# express_pre_power.net
KiCad netlist of a schematic drawn in Altium Designer
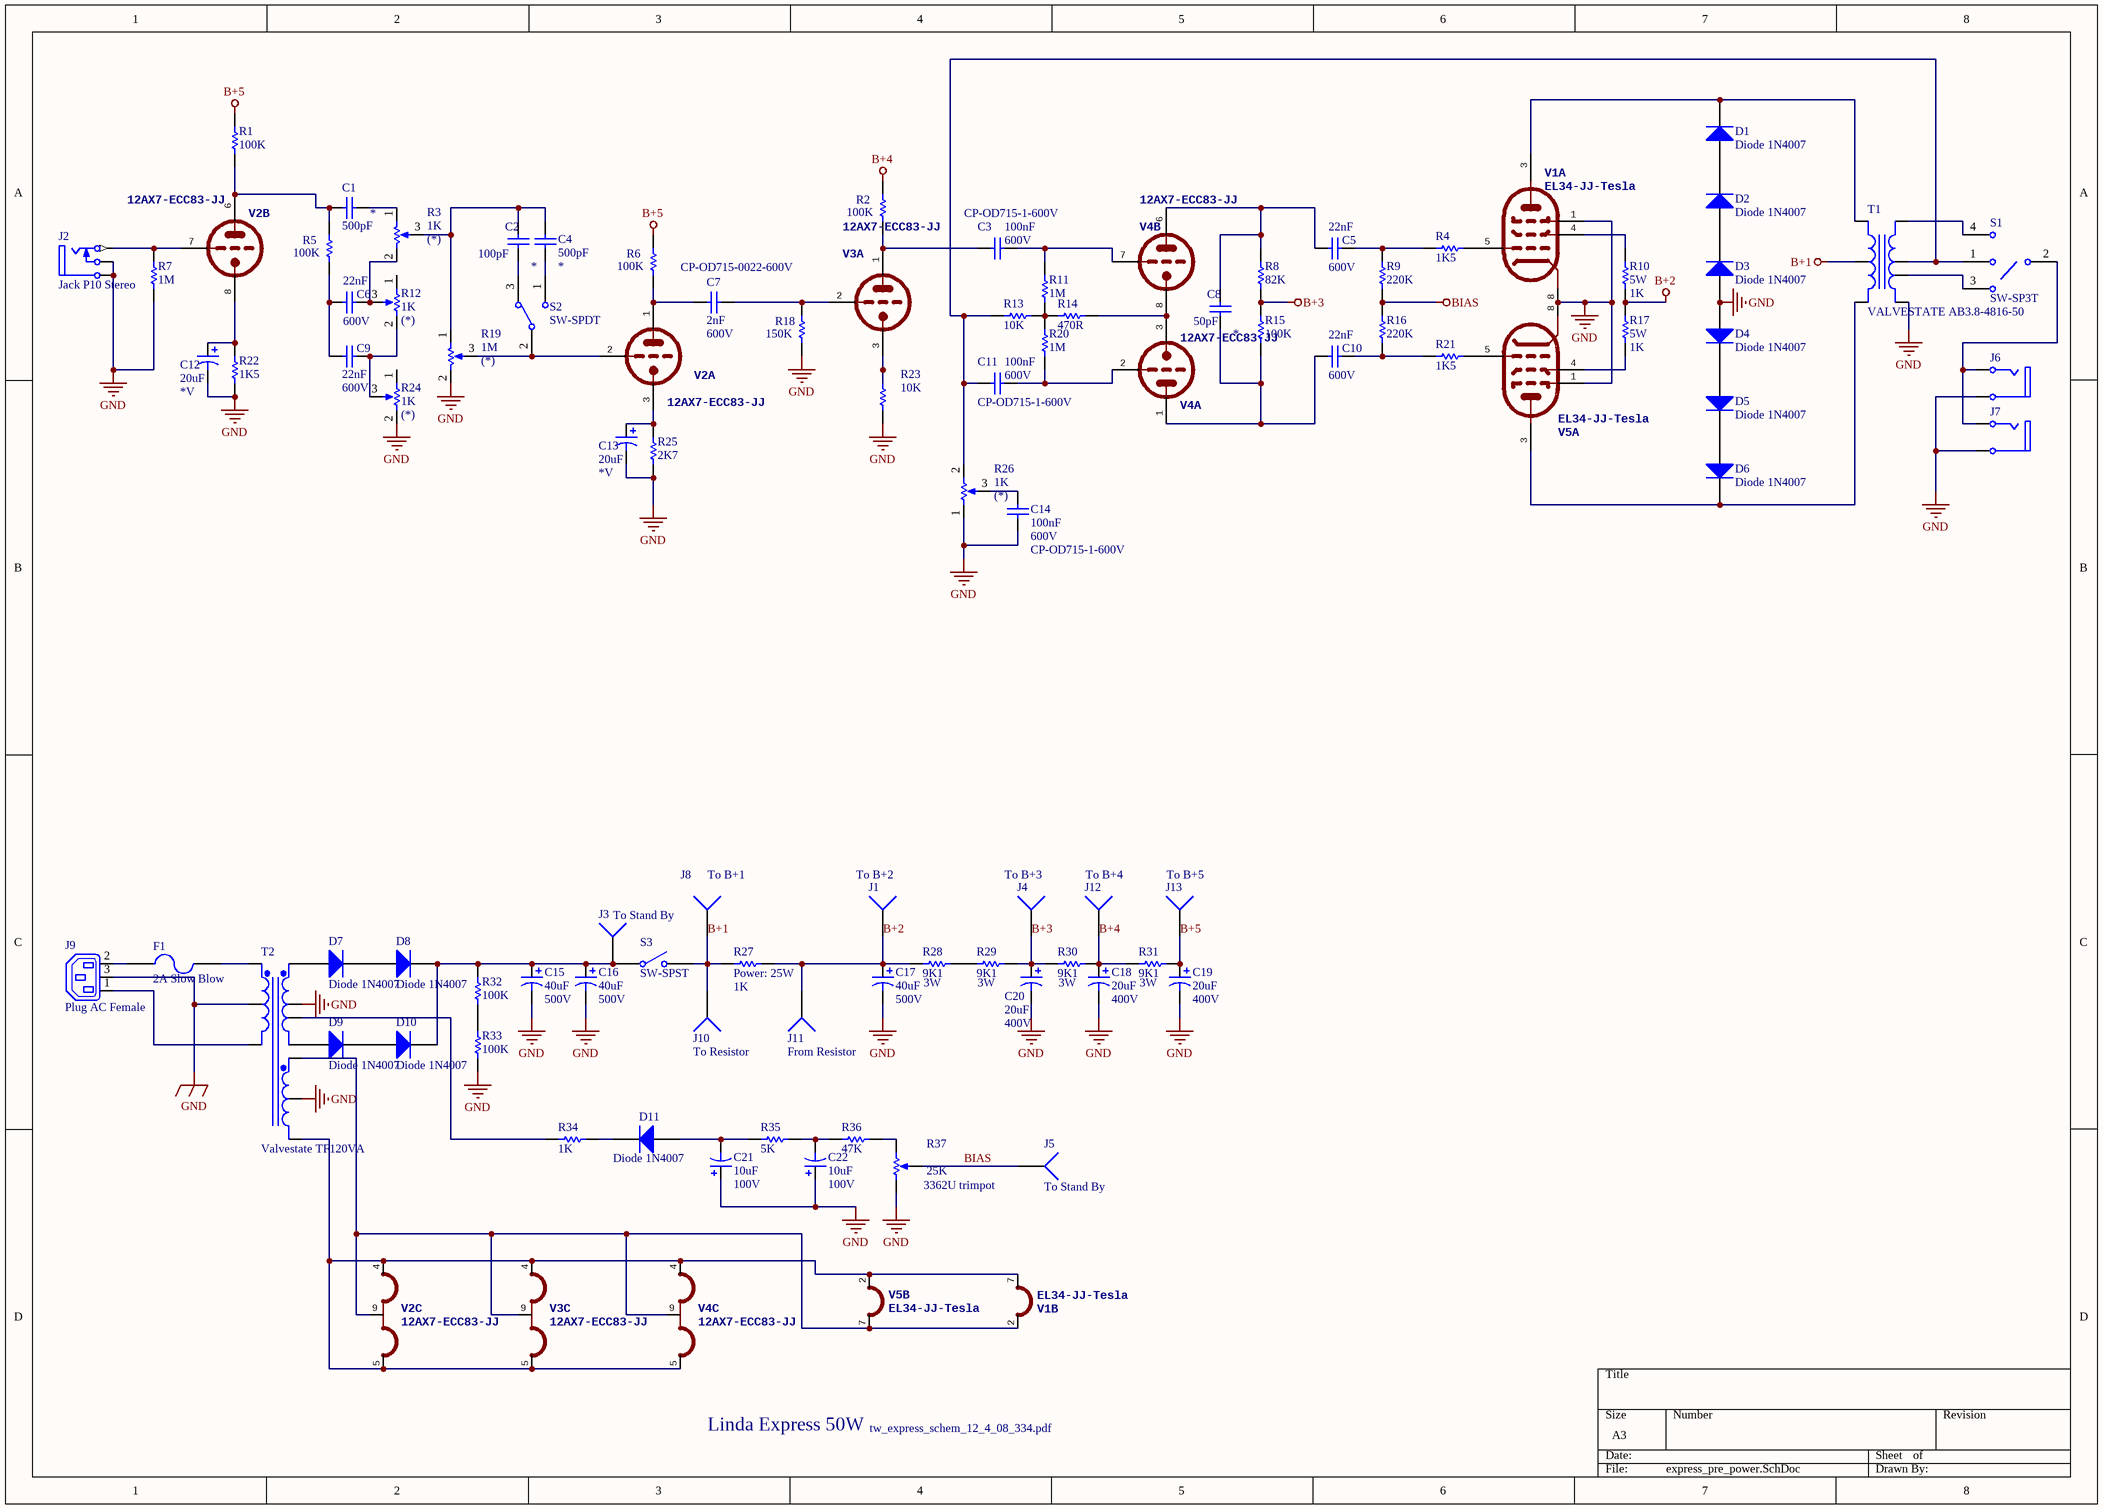
[diagram p0: express_pre_power.SchDoc]

(export (version "E")
  (design (tool "Eeschema 10.0.6"))
  (components
    (comp (ref "C1")
      (value "500pF")
      (footprint "Miscellaneous Devices:RAD-0.2")
      (description "Capacitor")
      (fields
        (field (name "VOLTAGE") "*")
        (field (name "Comment") "Ceramic Cap")
        (field (name "PUBLISHER") "Altium Limited")
      )
      (libsource (lib "capacitors") (part "Cap-Ceramic-Small"))
    )
    (comp (ref "C2")
      (value "100pF")
      (footprint "Miscellaneous Devices:RAD-0.2")
      (description "Capacitor")
      (fields
        (field (name "VOLTAGE") "*")
        (field (name "Comment") "Ceramic Cap")
        (field (name "PUBLISHER") "Altium Limited")
      )
      (libsource (lib "capacitors") (part "Cap-Ceramic-Small"))
    )
    (comp (ref "C3")
      (value "100nF")
      (footprint "ORANGE-DROP-100nF-600V")
      (description "Capacitor")
      (fields
        (field (name "MANUFACTURERPARTNUMBER") "715P10496L")
        (field (name "VOLTAGE") "600V")
        (field (name "TUBEDEPOT_SN") "CP-OD715-1-600V")
        (field (name "Comment") "Orange Drop Capacitor")
        (field (name "PUBLISHER") "Altium Limited")
      )
      (libsource (lib "capacitors") (part "Cap-Orange-DROP-100nF-600V"))
    )
    (comp (ref "C4")
      (value "500pF")
      (footprint "Miscellaneous Devices:RAD-0.2")
      (description "Capacitor")
      (fields
        (field (name "VOLTAGE") "*")
        (field (name "Comment") "Ceramic Cap")
        (field (name "PUBLISHER") "Altium Limited")
      )
      (libsource (lib "capacitors") (part "Cap-Ceramic-Small"))
    )
    (comp (ref "C5")
      (value "22nF")
      (footprint "ORANGE-DROP-22nF-600V")
      (description "Capacitor")
      (fields
        (field (name "MANUFACTURERPARTNUMBER") "715P22356KD3")
        (field (name "VOLTAGE") "600V")
        (field (name "Comment") "Orange Drop Capacitor")
        (field (name "PUBLISHER") "Linda HB Amplifiers")
      )
      (libsource (lib "capacitors") (part "Cap-Orange-DROP-22nF-600V"))
    )
    (comp (ref "C6")
      (value "22nF")
      (footprint "ORANGE-DROP-22nF-600V")
      (description "Capacitor")
      (fields
        (field (name "MANUFACTURERPARTNUMBER") "715P22356KD3")
        (field (name "VOLTAGE") "600V")
        (field (name "Comment") "Orange Drop Capacitor")
        (field (name "PUBLISHER") "Linda HB Amplifiers")
      )
      (libsource (lib "capacitors") (part "Cap-Orange-DROP-22nF-600V"))
    )
    (comp (ref "C7")
      (value "2nF")
      (footprint "ORANGE-DROP-2nF-600V")
      (description "Capacitor")
      (fields
        (field (name "MANUFACTURERPARTNUMBER") "715P22296J")
        (field (name "VOLTAGE") "600V")
        (field (name "TUBEDEPOTPN") "CP-OD715-0022-600V")
        (field (name "Comment") "Orange Drop Capacitor")
        (field (name "PUBLISHER") "Linda HB Amplifiers")
      )
      (libsource (lib "capacitors") (part "Cap-Orange-DROP-2nF-600V"))
    )
    (comp (ref "C8")
      (value "50pF")
      (footprint "Miscellaneous Devices:RAD-0.2")
      (description "Capacitor")
      (fields
        (field (name "VOLTAGE") "*")
        (field (name "Comment") "Ceramic Cap")
        (field (name "PUBLISHER") "Altium Limited")
      )
      (libsource (lib "capacitors") (part "Cap-Ceramic-Small"))
    )
    (comp (ref "C9")
      (value "22nF")
      (footprint "ORANGE-DROP-22nF-600V")
      (description "Capacitor")
      (fields
        (field (name "MANUFACTURERPARTNUMBER") "715P22356KD3")
        (field (name "VOLTAGE") "600V")
        (field (name "Comment") "Orange Drop Capacitor")
        (field (name "PUBLISHER") "Linda HB Amplifiers")
      )
      (libsource (lib "capacitors") (part "Cap-Orange-DROP-22nF-600V"))
    )
    (comp (ref "C10")
      (value "22nF")
      (footprint "ORANGE-DROP-22nF-600V")
      (description "Capacitor")
      (fields
        (field (name "MANUFACTURERPARTNUMBER") "715P22356KD3")
        (field (name "VOLTAGE") "600V")
        (field (name "Comment") "Orange Drop Capacitor")
        (field (name "PUBLISHER") "Linda HB Amplifiers")
      )
      (libsource (lib "capacitors") (part "Cap-Orange-DROP-22nF-600V"))
    )
    (comp (ref "C11")
      (value "100nF")
      (footprint "ORANGE-DROP-100nF-600V")
      (description "Capacitor")
      (fields
        (field (name "MANUFACTURERPARTNUMBER") "715P10496L")
        (field (name "VOLTAGE") "600V")
        (field (name "TUBEDEPOT_SN") "CP-OD715-1-600V")
        (field (name "Comment") "Orange Drop Capacitor")
        (field (name "PUBLISHER") "Altium Limited")
      )
      (libsource (lib "capacitors") (part "Cap-Orange-DROP-100nF-600V"))
    )
    (comp (ref "C12")
      (value "20uF")
      (footprint "AXIAL-POL-30mm")
      (description "Polarized Capacitor Axial")
      (fields
        (field (name "VOLTAGE") "*V")
        (field (name "Comment") "Cap Pol Axial")
        (field (name "PUBLISHER") "Whitesheep Amps")
      )
      (libsource (lib "capacitors") (part "Cap Pol Axial"))
    )
    (comp (ref "C13")
      (value "20uF")
      (footprint "AXIAL-POL-30mm")
      (description "Polarized Capacitor Axial")
      (fields
        (field (name "VOLTAGE") "*V")
        (field (name "Comment") "Cap Pol Axial")
        (field (name "PUBLISHER") "Whitesheep Amps")
      )
      (libsource (lib "capacitors") (part "Cap Pol Axial"))
    )
    (comp (ref "C14")
      (value "100nF")
      (footprint "ORANGE-DROP-100nF-600V")
      (description "Capacitor")
      (fields
        (field (name "MANUFACTURERPARTNUMBER") "715P10496L")
        (field (name "VOLTAGE") "600V")
        (field (name "TUBEDEPOT_SN") "CP-OD715-1-600V")
        (field (name "Comment") "Orange Drop Capacitor")
        (field (name "PUBLISHER") "Altium Limited")
      )
      (libsource (lib "capacitors") (part "Cap-Orange-DROP-100nF-600V"))
    )
    (comp (ref "C15")
      (value "40uF")
      (footprint "SPRAGUE-ATOM-40uF-500V")
      (description "Sprague Atom Eletrolitic 40uF Axial 500V")
      (fields (field (name "VOLTAGE") "500V") (field (name "PUBLISHER") "Whitesheep Amps"))
      (libsource (lib "capacitors") (part "Sprague Atom Eletrolitic 40uF Axial 500V"))
    )
    (comp (ref "C16")
      (value "40uF")
      (footprint "SPRAGUE-ATOM-40uF-500V")
      (description "Sprague Atom Eletrolitic 40uF Axial 500V")
      (fields (field (name "VOLTAGE") "500V") (field (name "PUBLISHER") "Whitesheep Amps"))
      (libsource (lib "capacitors") (part "Sprague Atom Eletrolitic 40uF Axial 500V"))
    )
    (comp (ref "C17")
      (value "40uF")
      (footprint "SPRAGUE-ATOM-40uF-500V")
      (description "Sprague Atom Eletrolitic 40uF Axial 500V")
      (fields (field (name "VOLTAGE") "500V") (field (name "PUBLISHER") "Whitesheep Amps"))
      (libsource (lib "capacitors") (part "Sprague Atom Eletrolitic 40uF Axial 500V"))
    )
    (comp (ref "C18")
      (value "20uF")
      (footprint "RAD-POL-7.6-15")
      (description "Polarized Capacitor (Axial)")
      (fields
        (field (name "VOLTAGE") "400V")
        (field (name "Comment") "Cap Pol Rad")
        (field (name "PUBLISHER") "Altium Limited")
      )
      (libsource (lib "capacitors") (part "Cap Pol Rad"))
    )
    (comp (ref "C19")
      (value "20uF")
      (footprint "RAD-POL-7.6-15")
      (description "Polarized Capacitor (Axial)")
      (fields
        (field (name "VOLTAGE") "400V")
        (field (name "Comment") "Cap Pol Rad")
        (field (name "PUBLISHER") "Altium Limited")
      )
      (libsource (lib "capacitors") (part "Cap Pol Rad"))
    )
    (comp (ref "C20")
      (value "20uF")
      (footprint "RAD-POL-7.6-15")
      (description "Polarized Capacitor (Axial)")
      (fields
        (field (name "VOLTAGE") "400V")
        (field (name "Comment") "Cap Pol Rad")
        (field (name "PUBLISHER") "Altium Limited")
      )
      (libsource (lib "capacitors") (part "Cap Pol Rad"))
    )
    (comp (ref "C21")
      (value "10uF")
      (footprint "RAD-POL-16x20x7.5")
      (description "Vishay 22uF 100V Polarized Capacitor (Radial); 2 Leads")
      (fields
        (field (name "PART NUMBER") "142 RHS")
        (field (name "VOLTAGE") "100V")
        (field (name "Comment") "Cap Pol Radial Vishay 22uF 100V")
        (field (name "PUBLISHER") "Altium Limited")
      )
      (libsource (lib "capacitors") (part "Cap Pol Radial Vishay 22uF 100V"))
    )
    (comp (ref "C22")
      (value "10uF")
      (footprint "RAD-POL-16x20x7.5")
      (description "Vishay 22uF 100V Polarized Capacitor (Radial); 2 Leads")
      (fields
        (field (name "PART NUMBER") "142 RHS")
        (field (name "VOLTAGE") "100V")
        (field (name "Comment") "Cap Pol Radial Vishay 22uF 100V")
        (field (name "PUBLISHER") "Altium Limited")
      )
      (libsource (lib "capacitors") (part "Cap Pol Radial Vishay 22uF 100V"))
    )
    (comp (ref "D1")
      (value "Diode 1N4007")
      (footprint "1N4007-10.46mm Diode")
      (description "1 Amp General Purpose Rectifier")
      (fields (field (name "PUBLISHER") "Altium Limited"))
      (libsource (lib "diodes") (part "Diode 1N4007"))
    )
    (comp (ref "D2")
      (value "Diode 1N4007")
      (footprint "1N4007-10.46mm Diode")
      (description "1 Amp General Purpose Rectifier")
      (fields (field (name "PUBLISHER") "Altium Limited"))
      (libsource (lib "diodes") (part "Diode 1N4007"))
    )
    (comp (ref "D3")
      (value "Diode 1N4007")
      (footprint "1N4007-10.46mm Diode")
      (description "1 Amp General Purpose Rectifier")
      (fields (field (name "PUBLISHER") "Altium Limited"))
      (libsource (lib "diodes") (part "Diode 1N4007"))
    )
    (comp (ref "D4")
      (value "Diode 1N4007")
      (footprint "1N4007-10.46mm Diode")
      (description "1 Amp General Purpose Rectifier")
      (fields (field (name "PUBLISHER") "Altium Limited"))
      (libsource (lib "diodes") (part "Diode 1N4007"))
    )
    (comp (ref "D5")
      (value "Diode 1N4007")
      (footprint "1N4007-10.46mm Diode")
      (description "1 Amp General Purpose Rectifier")
      (fields (field (name "PUBLISHER") "Altium Limited"))
      (libsource (lib "diodes") (part "Diode 1N4007"))
    )
    (comp (ref "D6")
      (value "Diode 1N4007")
      (footprint "1N4007-10.46mm Diode")
      (description "1 Amp General Purpose Rectifier")
      (fields (field (name "PUBLISHER") "Altium Limited"))
      (libsource (lib "diodes") (part "Diode 1N4007"))
    )
    (comp (ref "D7")
      (value "Diode 1N4007")
      (footprint "1N4007-10.46mm Diode")
      (description "1 Amp General Purpose Rectifier")
      (fields (field (name "PUBLISHER") "Altium Limited"))
      (libsource (lib "diodes") (part "Diode 1N4007"))
    )
    (comp (ref "D8")
      (value "Diode 1N4007")
      (footprint "1N4007-10.46mm Diode")
      (description "1 Amp General Purpose Rectifier")
      (fields (field (name "PUBLISHER") "Altium Limited"))
      (libsource (lib "diodes") (part "Diode 1N4007"))
    )
    (comp (ref "D9")
      (value "Diode 1N4007")
      (footprint "1N4007-10.46mm Diode")
      (description "1 Amp General Purpose Rectifier")
      (fields (field (name "PUBLISHER") "Altium Limited"))
      (libsource (lib "diodes") (part "Diode 1N4007"))
    )
    (comp (ref "D10")
      (value "Diode 1N4007")
      (footprint "1N4007-10.46mm Diode")
      (description "1 Amp General Purpose Rectifier")
      (fields (field (name "PUBLISHER") "Altium Limited"))
      (libsource (lib "diodes") (part "Diode 1N4007"))
    )
    (comp (ref "D11")
      (value "Diode 1N4007")
      (footprint "1N4007-10.46mm Diode")
      (description "1 Amp General Purpose Rectifier")
      (fields (field (name "PUBLISHER") "Altium Limited"))
      (libsource (lib "diodes") (part "Diode 1N4007"))
    )
    (comp (ref "F1")
      (value "2A Slow Blow")
      (footprint "FUSE-PCB-5x20mm")
      (description "Fuse")
      (fields (field (name "PUBLISHER") "Altium Limited"))
      (libsource (lib "fuses") (part "Fuse 2"))
    )
    (comp (ref "J1")
      (value "To B+2")
      (footprint "PIN1")
      (description "Socket")
      (fields (field (name "PUBLISHER") "Altium Limited"))
      (libsource (lib "Miscellaneous Connectors") (part "Socket"))
    )
    (comp (ref "J2")
      (value "Jack P10 Stereo")
      (footprint "JACK-STEREO-3PAD")
      (description "Jack Socket, 1/4\" [6.5mm], Thru-Hole, Vertical, 2-Conductor with Tip closed")
      (fields (field (name "PUBLISHER") "Altium Limited"))
      (libsource (lib "jacks") (part "Jack P10 Stereo"))
    )
    (comp (ref "J3")
      (value "To Stand By")
      (footprint "PIN1")
      (description "Socket")
      (fields (field (name "PUBLISHER") "Altium Limited"))
      (libsource (lib "Miscellaneous Connectors") (part "Socket"))
    )
    (comp (ref "J4")
      (value "To B+3")
      (footprint "PIN1")
      (description "Socket")
      (fields (field (name "PUBLISHER") "Altium Limited"))
      (libsource (lib "Miscellaneous Connectors") (part "Socket"))
    )
    (comp (ref "J5")
      (value "To Stand By")
      (footprint "PIN1")
      (description "Socket")
      (fields (field (name "PUBLISHER") "Altium Limited"))
      (libsource (lib "Miscellaneous Connectors") (part "Socket"))
    )
    (comp (ref "J6")
      (value "Jack Mono")
      (footprint "JACK-STEREO-3PAD")
      (description "Jack Socket, Thru-Hole, Vertical, 2-Conductor Open Circuit")
      (fields (field (name "PUBLISHER") "Altium Limited"))
      (libsource (lib "jacks") (part "Jack Mono P10"))
    )
    (comp (ref "J7")
      (value "Jack Mono")
      (footprint "JACK-STEREO-3PAD")
      (description "Jack Socket, Thru-Hole, Vertical, 2-Conductor Open Circuit")
      (fields (field (name "PUBLISHER") "Altium Limited"))
      (libsource (lib "jacks") (part "Jack Mono P10"))
    )
    (comp (ref "J8")
      (value "To B+1")
      (footprint "PIN1")
      (description "Socket")
      (fields (field (name "PUBLISHER") "Altium Limited"))
      (libsource (lib "Miscellaneous Connectors") (part "Socket"))
    )
    (comp (ref "J9")
      (value "Plug AC Female")
      (footprint "IEC7-2H3")
      (description "IEC Mains Power Outlet, EN60 320-2-2 F Class I, PC Flange Rear Mount, Chassis Socket")
      (fields (field (name "PUBLISHER") "Altium Limited"))
      (libsource (lib "Miscellaneous Connectors") (part "Plug AC Female"))
    )
    (comp (ref "J10")
      (value "To Resistor")
      (footprint "PIN1")
      (description "Socket")
      (fields (field (name "PUBLISHER") "Altium Limited"))
      (libsource (lib "Miscellaneous Connectors") (part "Socket"))
    )
    (comp (ref "J11")
      (value "From Resistor")
      (footprint "PIN1")
      (description "Socket")
      (fields (field (name "PUBLISHER") "Altium Limited"))
      (libsource (lib "Miscellaneous Connectors") (part "Socket"))
    )
    (comp (ref "J12")
      (value "To B+4")
      (footprint "PIN1")
      (description "Socket")
      (fields (field (name "PUBLISHER") "Altium Limited"))
      (libsource (lib "Miscellaneous Connectors") (part "Socket"))
    )
    (comp (ref "J13")
      (value "To B+5")
      (footprint "PIN1")
      (description "Socket")
      (fields (field (name "PUBLISHER") "Altium Limited"))
      (libsource (lib "Miscellaneous Connectors") (part "Socket"))
    )
    (comp (ref "R1")
      (value "100K")
      (footprint "AXIAL-0.6")
      (description "Semiconductor Resistor")
      (fields
        (field (name "POWER") "1/2W")
        (field (name "Comment") "Metal Film Resistor 1/2W")
        (field (name "PUBLISHER") "Whitesheep Amps")
      )
      (libsource (lib "resistors") (part "Res Metal Film 1/2W"))
    )
    (comp (ref "R2")
      (value "100K")
      (footprint "AXIAL-0.6")
      (description "Semiconductor Resistor")
      (fields
        (field (name "POWER") "1/2W")
        (field (name "Comment") "Metal Film Resistor 1/2W")
        (field (name "PUBLISHER") "Whitesheep Amps")
      )
      (libsource (lib "resistors") (part "Res Metal Film 1/2W"))
    )
    (comp (ref "R3")
      (value "1K")
      (footprint "pot_alpha")
      (description "Potentiometer")
      (fields
        (field (name "TYPE") "(*)")
        (field (name "Comment") "ALPHA Potentiometer")
        (field (name "PUBLISHER") "Altium Limited")
      )
      (libsource (lib "potentiometers") (part "alpha-pot"))
    )
    (comp (ref "R4")
      (value "1K5")
      (footprint "AXIAL-0.6")
      (description "Semiconductor Resistor")
      (fields
        (field (name "POWER") "1/2W")
        (field (name "Comment") "Metal Film Resistor 1/2W")
        (field (name "PUBLISHER") "Whitesheep Amps")
      )
      (libsource (lib "resistors") (part "Res Metal Film 1/2W"))
    )
    (comp (ref "R5")
      (value "100K")
      (footprint "AXIAL-0.6")
      (description "Semiconductor Resistor")
      (fields
        (field (name "POWER") "1/2W")
        (field (name "Comment") "Metal Film Resistor 1/2W")
        (field (name "PUBLISHER") "Whitesheep Amps")
      )
      (libsource (lib "resistors") (part "Res Metal Film 1/2W"))
    )
    (comp (ref "R6")
      (value "100K")
      (footprint "AXIAL-0.6")
      (description "Semiconductor Resistor")
      (fields
        (field (name "POWER") "1/2W")
        (field (name "Comment") "Metal Film Resistor 1/2W")
        (field (name "PUBLISHER") "Whitesheep Amps")
      )
      (libsource (lib "resistors") (part "Res Metal Film 1/2W"))
    )
    (comp (ref "R7")
      (value "1M")
      (footprint "AXIAL-0.6")
      (description "Semiconductor Resistor")
      (fields
        (field (name "POWER") "1/2W")
        (field (name "Comment") "Metal Film Resistor 1/2W")
        (field (name "PUBLISHER") "Whitesheep Amps")
      )
      (libsource (lib "resistors") (part "Res Metal Film 1/2W"))
    )
    (comp (ref "R8")
      (value "82K")
      (footprint "AXIAL-0.6")
      (description "Semiconductor Resistor")
      (fields
        (field (name "POWER") "1/2W")
        (field (name "Comment") "Metal Film Resistor 1/2W")
        (field (name "PUBLISHER") "Whitesheep Amps")
      )
      (libsource (lib "resistors") (part "Res Metal Film 1/2W"))
    )
    (comp (ref "R9")
      (value "220K")
      (footprint "AXIAL-0.6")
      (description "Semiconductor Resistor")
      (fields
        (field (name "POWER") "1/2W")
        (field (name "Comment") "Metal Film Resistor 1/2W")
        (field (name "PUBLISHER") "Whitesheep Amps")
      )
      (libsource (lib "resistors") (part "Res Metal Film 1/2W"))
    )
    (comp (ref "R10")
      (value "1K")
      (footprint "Resistor Vishay 5W 1k Power Wirewound")
      (description "Semiconductor Resistor")
      (fields
        (field (name "POWER") "5W")
        (field (name "Comment") "Wire Wound Power Resistor")
        (field (name "PUBLISHER") "Whitesheep Amps")
      )
      (libsource (lib "resistors") (part "Res Wire Wound Power Resistor 5W"))
    )
    (comp (ref "R11")
      (value "1M")
      (footprint "AXIAL-0.6")
      (description "Semiconductor Resistor")
      (fields
        (field (name "POWER") "1/2W")
        (field (name "Comment") "Metal Film Resistor 1/2W")
        (field (name "PUBLISHER") "Whitesheep Amps")
      )
      (libsource (lib "resistors") (part "Res Metal Film 1/2W"))
    )
    (comp (ref "R12")
      (value "1K")
      (footprint "pot_alpha")
      (description "Potentiometer")
      (fields
        (field (name "TYPE") "(*)")
        (field (name "Comment") "ALPHA Potentiometer")
        (field (name "PUBLISHER") "Altium Limited")
      )
      (libsource (lib "potentiometers") (part "alpha-pot"))
    )
    (comp (ref "R13")
      (value "10K")
      (footprint "AXIAL-0.6")
      (description "Semiconductor Resistor")
      (fields
        (field (name "POWER") "1/2W")
        (field (name "Comment") "Metal Film Resistor 1/2W")
        (field (name "PUBLISHER") "Whitesheep Amps")
      )
      (libsource (lib "resistors") (part "Res Metal Film 1/2W"))
    )
    (comp (ref "R14")
      (value "470R")
      (footprint "AXIAL-0.6")
      (description "Semiconductor Resistor")
      (fields
        (field (name "POWER") "1/2W")
        (field (name "Comment") "Metal Film Resistor 1/2W")
        (field (name "PUBLISHER") "Whitesheep Amps")
      )
      (libsource (lib "resistors") (part "Res Metal Film 1/2W"))
    )
    (comp (ref "R15")
      (value "100K")
      (footprint "AXIAL-0.6")
      (description "Semiconductor Resistor")
      (fields
        (field (name "POWER") "1/2W")
        (field (name "Comment") "Metal Film Resistor 1/2W")
        (field (name "PUBLISHER") "Whitesheep Amps")
      )
      (libsource (lib "resistors") (part "Res Metal Film 1/2W"))
    )
    (comp (ref "R16")
      (value "220K")
      (footprint "AXIAL-0.6")
      (description "Semiconductor Resistor")
      (fields
        (field (name "POWER") "1/2W")
        (field (name "Comment") "Metal Film Resistor 1/2W")
        (field (name "PUBLISHER") "Whitesheep Amps")
      )
      (libsource (lib "resistors") (part "Res Metal Film 1/2W"))
    )
    (comp (ref "R17")
      (value "1K")
      (footprint "Resistor Vishay 5W 1k Power Wirewound")
      (description "Semiconductor Resistor")
      (fields
        (field (name "POWER") "5W")
        (field (name "Comment") "Wire Wound Power Resistor")
        (field (name "PUBLISHER") "Whitesheep Amps")
      )
      (libsource (lib "resistors") (part "Res Wire Wound Power Resistor 5W"))
    )
    (comp (ref "R18")
      (value "150K")
      (footprint "AXIAL-0.6")
      (description "Semiconductor Resistor")
      (fields
        (field (name "POWER") "1/2W")
        (field (name "Comment") "Metal Film Resistor 1/2W")
        (field (name "PUBLISHER") "Whitesheep Amps")
      )
      (libsource (lib "resistors") (part "Res Metal Film 1/2W"))
    )
    (comp (ref "R19")
      (value "1M")
      (footprint "pot_alpha")
      (description "Potentiometer")
      (fields
        (field (name "TYPE") "(*)")
        (field (name "Comment") "ALPHA Potentiometer")
        (field (name "PUBLISHER") "Altium Limited")
      )
      (libsource (lib "potentiometers") (part "alpha-pot"))
    )
    (comp (ref "R20")
      (value "1M")
      (footprint "AXIAL-0.6")
      (description "Semiconductor Resistor")
      (fields
        (field (name "POWER") "1/2W")
        (field (name "Comment") "Metal Film Resistor 1/2W")
        (field (name "PUBLISHER") "Whitesheep Amps")
      )
      (libsource (lib "resistors") (part "Res Metal Film 1/2W"))
    )
    (comp (ref "R21")
      (value "1K5")
      (footprint "AXIAL-0.6")
      (description "Semiconductor Resistor")
      (fields
        (field (name "POWER") "1/2W")
        (field (name "Comment") "Metal Film Resistor 1/2W")
        (field (name "PUBLISHER") "Whitesheep Amps")
      )
      (libsource (lib "resistors") (part "Res Metal Film 1/2W"))
    )
    (comp (ref "R22")
      (value "1K5")
      (footprint "AXIAL-0.6")
      (description "Semiconductor Resistor")
      (fields
        (field (name "POWER") "1/2W")
        (field (name "Comment") "Metal Film Resistor 1/2W")
        (field (name "PUBLISHER") "Whitesheep Amps")
      )
      (libsource (lib "resistors") (part "Res Metal Film 1/2W"))
    )
    (comp (ref "R23")
      (value "10K")
      (footprint "AXIAL-0.6")
      (description "Semiconductor Resistor")
      (fields
        (field (name "POWER") "1/2W")
        (field (name "Comment") "Metal Film Resistor 1/2W")
        (field (name "PUBLISHER") "Whitesheep Amps")
      )
      (libsource (lib "resistors") (part "Res Metal Film 1/2W"))
    )
    (comp (ref "R24")
      (value "1K")
      (footprint "pot_alpha")
      (description "Potentiometer")
      (fields
        (field (name "TYPE") "(*)")
        (field (name "Comment") "ALPHA Potentiometer")
        (field (name "PUBLISHER") "Altium Limited")
      )
      (libsource (lib "potentiometers") (part "alpha-pot"))
    )
    (comp (ref "R25")
      (value "2K7")
      (footprint "AXIAL-0.6")
      (description "Semiconductor Resistor")
      (fields
        (field (name "POWER") "1/2W")
        (field (name "Comment") "Metal Film Resistor 1/2W")
        (field (name "PUBLISHER") "Whitesheep Amps")
      )
      (libsource (lib "resistors") (part "Res Metal Film 1/2W"))
    )
    (comp (ref "R26")
      (value "1K")
      (footprint "pot_alpha")
      (description "Potentiometer")
      (fields
        (field (name "TYPE") "(*)")
        (field (name "Comment") "ALPHA Potentiometer")
        (field (name "PUBLISHER") "Altium Limited")
      )
      (libsource (lib "potentiometers") (part "alpha-pot"))
    )
    (comp (ref "R27")
      (value "1K")
      (footprint "Power Wirewound Resistor 10W - Vishay Dale")
      (description "Semiconductor Resistor")
      (fields
        (field (name "POWER") "25W")
        (field (name "Comment") "Wire Wound Power Resistor")
        (field (name "PUBLISHER") "Whitesheep Amps")
      )
      (libsource (lib "resistors") (part "Res Vishay Dale Wire Wound Power Resistor 10R 10W"))
    )
    (comp (ref "R28")
      (value "9K1")
      (footprint "RESISTOR-MetalOxide-3W")
      (description "Semiconductor Resistor")
      (fields
        (field (name "POWER") "3W")
        (field (name "Comment") "Metal Film Resistor 1/2W")
        (field (name "PUBLISHER") "Linda HandBuilt Amplifiers")
      )
      (libsource (lib "resistors") (part "Res Metal Oxide 3W"))
    )
    (comp (ref "R29")
      (value "9K1")
      (footprint "RESISTOR-MetalOxide-3W")
      (description "Semiconductor Resistor")
      (fields
        (field (name "POWER") "3W")
        (field (name "Comment") "Metal Film Resistor 1/2W")
        (field (name "PUBLISHER") "Linda HandBuilt Amplifiers")
      )
      (libsource (lib "resistors") (part "Res Metal Oxide 3W"))
    )
    (comp (ref "R30")
      (value "9K1")
      (footprint "RESISTOR-MetalOxide-3W")
      (description "Semiconductor Resistor")
      (fields
        (field (name "POWER") "3W")
        (field (name "Comment") "Metal Film Resistor 1/2W")
        (field (name "PUBLISHER") "Linda HandBuilt Amplifiers")
      )
      (libsource (lib "resistors") (part "Res Metal Oxide 3W"))
    )
    (comp (ref "R31")
      (value "9K1")
      (footprint "RESISTOR-MetalOxide-3W")
      (description "Semiconductor Resistor")
      (fields
        (field (name "POWER") "3W")
        (field (name "Comment") "Metal Film Resistor 1/2W")
        (field (name "PUBLISHER") "Linda HandBuilt Amplifiers")
      )
      (libsource (lib "resistors") (part "Res Metal Oxide 3W"))
    )
    (comp (ref "R32")
      (value "100K")
      (footprint "RESISTOR-MetalOxide-3W")
      (description "Semiconductor Resistor")
      (fields
        (field (name "POWER") "1/2W")
        (field (name "Comment") "Metal Film Resistor 1/2W")
        (field (name "PUBLISHER") "Linda HandBuilt Amplifiers")
      )
      (libsource (lib "resistors") (part "Res Metal Oxide 3W"))
    )
    (comp (ref "R33")
      (value "100K")
      (footprint "RESISTOR-MetalOxide-3W")
      (description "Semiconductor Resistor")
      (fields
        (field (name "POWER") "1/2W")
        (field (name "Comment") "Metal Film Resistor 1/2W")
        (field (name "PUBLISHER") "Linda HandBuilt Amplifiers")
      )
      (libsource (lib "resistors") (part "Res Metal Oxide 3W"))
    )
    (comp (ref "R34")
      (value "1K")
      (footprint "RESISTOR-MetalOxide-3W")
      (description "Semiconductor Resistor")
      (fields
        (field (name "POWER") "1/2W")
        (field (name "Comment") "Metal Film Resistor 1/2W")
        (field (name "PUBLISHER") "Linda HandBuilt Amplifiers")
      )
      (libsource (lib "resistors") (part "Res Metal Oxide 3W"))
    )
    (comp (ref "R35")
      (value "5K")
      (footprint "RESISTOR-MetalOxide-3W")
      (description "Semiconductor Resistor")
      (fields
        (field (name "POWER") "1/2W")
        (field (name "Comment") "Metal Film Resistor 1/2W")
        (field (name "PUBLISHER") "Linda HandBuilt Amplifiers")
      )
      (libsource (lib "resistors") (part "Res Metal Oxide 3W"))
    )
    (comp (ref "R36")
      (value "47K")
      (footprint "RESISTOR-MetalOxide-3W")
      (description "Semiconductor Resistor")
      (fields
        (field (name "POWER") "1/2W")
        (field (name "Comment") "Metal Film Resistor 1/2W")
        (field (name "PUBLISHER") "Linda HandBuilt Amplifiers")
      )
      (libsource (lib "resistors") (part "Res Metal Oxide 3W"))
    )
    (comp (ref "R37")
      (value "3362U trimpot")
      (footprint "33262U trimpot")
      (description "3362U Timpot")
      (fields (field (name "ALTIUM_VALUE") "25K") (field (name "PUBLISHER") "Linda Hand Build Amplification"))
      (libsource (lib "potentiometers") (part "3362U trimpot"))
    )
    (comp (ref "S1")
      (value "SW-SP3T")
      (footprint "TL36WW15050")
      (description "SPDT Subminiature Toggle Switch, Right Angle Mounting, Vertical Actuation")
      (fields (field (name "PUBLISHER") "Altium Limited"))
      (libsource (lib "switches") (part "SW-SP3T"))
    )
    (comp (ref "S2")
      (value "SW-SPDT")
      (footprint "SPDT")
      (description "SPDT Subminiature Toggle Switch, Right Angle Mounting, Vertical Actuation")
      (fields (field (name "PUBLISHER") "Altium Limited"))
      (libsource (lib "switches") (part "SW-SPDT"))
    )
    (comp (ref "S3")
      (value "SW-SPST")
      (footprint "SPST-2")
      (description "Single-Pole, Single-Throw Switch")
      (fields (field (name "PUBLISHER") "Altium Limited"))
      (libsource (lib "Miscellaneous Devices") (part "SW-SPST"))
    )
    (comp (ref "T1")
      (value "Output Transformer")
      (footprint "VALVESTATE-AB3.8-4816-50")
      (description "VALVESTATE AB3.8-4816-50")
      (fields
        (field (name "PARTNUMBER") "VALVESTATE AB3.8-4816-50")
        (field (name "PUBLISHER") "LINDA Hand Built Amplifiers")
      )
      (libsource (lib "trafo") (part "VALVESTATE AB3.8-4816-50"))
    )
    (comp (ref "T2")
      (value "Valvestate TF120VA")
      (footprint "TRF_10")
      (description "VALVESTATE TF 120VA")
      (fields (field (name "PUBLISHER") "LINDA Hand Built Amplifiers"))
      (libsource (lib "trafo") (part "Valvestate TF120VA"))
    )
    (comp (ref "V1")
      (value "EL34-JJ-Tesla")
      (footprint "EL34-JJ")
      (libsource (lib "") (part "EL34-JJ-Tesla_1"))
    )
    (comp (ref "V2")
      (value "12AX7-ECC83-JJ")
      (footprint "12AX7(ECC83)-JJ Tesla")
      (libsource (lib "eagle_tubes_v6") (part "12AX7-ECC83-JJ"))
    )
    (comp (ref "V3")
      (value "12AX7-ECC83-JJ")
      (footprint "12AX7(ECC83)-JJ Tesla")
      (libsource (lib "eagle_tubes_v6") (part "12AX7-ECC83-JJ"))
    )
    (comp (ref "V4")
      (value "12AX7-ECC83-JJ")
      (footprint "12AX7(ECC83)-JJ Tesla")
      (libsource (lib "eagle_tubes_v6") (part "12AX7-ECC83-JJ"))
    )
    (comp (ref "V5")
      (value "EL34-JJ-Tesla")
      (footprint "EL34-JJ")
      (libsource (lib "eagle_tubes_v6") (part "EL34-JJ-Tesla"))
    )
  )
  (nets
    (net (code "1") (name "B+1") (class "Default")
      (node (ref "J10") (pin "1") (pinfunction "1_1") (pintype "passive"))
      (node (ref "J8") (pin "1") (pinfunction "1_1") (pintype "passive"))
      (node (ref "R27") (pin "1") (pinfunction "1_1") (pintype "passive"))
      (node (ref "S3") (pin "2") (pinfunction "NO_2") (pintype "passive"))
      (node (ref "T1") (pin "2") (pinfunction "B+_2") (pintype "passive"))
    )
    (net (code "2") (name "B+2") (class "Default")
      (node (ref "C17") (pin "1") (pinfunction "1_1") (pintype "passive"))
      (node (ref "J1") (pin "1") (pinfunction "1_1") (pintype "passive"))
      (node (ref "J11") (pin "1") (pinfunction "1_1") (pintype "passive"))
      (node (ref "R10") (pin "1") (pinfunction "1_1") (pintype "passive"))
      (node (ref "R17") (pin "2") (pinfunction "2_2") (pintype "passive"))
      (node (ref "R27") (pin "2") (pinfunction "2_2") (pintype "passive"))
      (node (ref "R28") (pin "1") (pinfunction "1_1") (pintype "passive"))
    )
    (net (code "3") (name "B+3") (class "Default")
      (node (ref "C20") (pin "1") (pinfunction "1_1") (pintype "passive"))
      (node (ref "J4") (pin "1") (pinfunction "1_1") (pintype "passive"))
      (node (ref "R15") (pin "2") (pinfunction "2_2") (pintype "passive"))
      (node (ref "R29") (pin "2") (pinfunction "2_2") (pintype "passive"))
      (node (ref "R30") (pin "1") (pinfunction "1_1") (pintype "passive"))
      (node (ref "R8") (pin "1") (pinfunction "1_1") (pintype "passive"))
    )
    (net (code "4") (name "B+4") (class "Default")
      (node (ref "C18") (pin "1") (pinfunction "1_1") (pintype "passive"))
      (node (ref "J12") (pin "1") (pinfunction "1_1") (pintype "passive"))
      (node (ref "R2") (pin "2") (pinfunction "2_2") (pintype "passive"))
      (node (ref "R30") (pin "2") (pinfunction "2_2") (pintype "passive"))
      (node (ref "R31") (pin "1") (pinfunction "1_1") (pintype "passive"))
    )
    (net (code "5") (name "B+5") (class "Default")
      (node (ref "C19") (pin "1") (pinfunction "1_1") (pintype "passive"))
      (node (ref "J13") (pin "1") (pinfunction "1_1") (pintype "passive"))
      (node (ref "R1") (pin "2") (pinfunction "2_2") (pintype "passive"))
      (node (ref "R31") (pin "2") (pinfunction "2_2") (pintype "passive"))
      (node (ref "R6") (pin "2") (pinfunction "2_2") (pintype "passive"))
    )
    (net (code "6") (name "BIAS") (class "Default")
      (node (ref "J5") (pin "1") (pinfunction "1_1") (pintype "passive"))
      (node (ref "R16") (pin "2") (pinfunction "2_2") (pintype "passive"))
      (node (ref "R37") (pin "3") (pinfunction "TAP_3") (pintype "passive"))
      (node (ref "R9") (pin "1") (pinfunction "1_1") (pintype "passive"))
    )
    (net (code "7") (name "GND") (class "Default")
      (node (ref "C12") (pin "2") (pinfunction "2_2") (pintype "passive"))
      (node (ref "C13") (pin "2") (pinfunction "2_2") (pintype "passive"))
      (node (ref "C14") (pin "1") (pinfunction "1_1") (pintype "passive"))
      (node (ref "C15") (pin "2") (pinfunction "2_2") (pintype "passive"))
      (node (ref "C16") (pin "2") (pinfunction "2_2") (pintype "passive"))
      (node (ref "C17") (pin "2") (pinfunction "2_2") (pintype "passive"))
      (node (ref "C18") (pin "2") (pinfunction "2_2") (pintype "passive"))
      (node (ref "C19") (pin "2") (pinfunction "2_2") (pintype "passive"))
      (node (ref "C20") (pin "2") (pinfunction "2_2") (pintype "passive"))
      (node (ref "C21") (pin "1") (pinfunction "1_1") (pintype "passive"))
      (node (ref "C22") (pin "1") (pinfunction "1_1") (pintype "passive"))
      (node (ref "D3") (pin "1") (pinfunction "A_1") (pintype "passive"))
      (node (ref "D4") (pin "1") (pinfunction "A_1") (pintype "passive"))
      (node (ref "J2") (pin "2") (pinfunction "TN_2") (pintype "passive"))
      (node (ref "J2") (pin "5") (pinfunction "S_5") (pintype "power_in"))
      (node (ref "J6") (pin "2") (pinfunction "S_2") (pintype "power_in"))
      (node (ref "J7") (pin "2") (pinfunction "S_2") (pintype "power_in"))
      (node (ref "J9") (pin "3") (pinfunction "E_3") (pintype "power_in"))
      (node (ref "R18") (pin "1") (pinfunction "1_1") (pintype "passive"))
      (node (ref "R19") (pin "2") (pinfunction "BOT_2") (pintype "passive"))
      (node (ref "R22") (pin "1") (pinfunction "1_1") (pintype "passive"))
      (node (ref "R23") (pin "1") (pinfunction "1_1") (pintype "passive"))
      (node (ref "R24") (pin "2") (pinfunction "BOT_2") (pintype "passive"))
      (node (ref "R25") (pin "1") (pinfunction "1_1") (pintype "passive"))
      (node (ref "R26") (pin "1") (pinfunction "TOP_1") (pintype "passive"))
      (node (ref "R33") (pin "1") (pinfunction "1_1") (pintype "passive"))
      (node (ref "R37") (pin "1") (pinfunction "TOP_1") (pintype "passive"))
      (node (ref "R7") (pin "1") (pinfunction "1_1") (pintype "passive"))
      (node (ref "T1") (pin "7") (pinfunction "Common_7") (pintype "passive"))
      (node (ref "T2") (pin "2") (pinfunction "Pri+_127V_2") (pintype "passive"))
      (node (ref "T2") (pin "5") (pinfunction "SEC_CT_5") (pintype "passive"))
      (node (ref "T2") (pin "9") (pinfunction "3.15V_CT_9") (pintype "passive"))
      (node (ref "V1") (pin "1") (pinfunction "PBG_1") (pintype "passive"))
      (node (ref "V1") (pin "8") (pinfunction "PK_8") (pintype "passive"))
      (node (ref "V5") (pin "1") (pinfunction "PBG_1") (pintype "passive"))
      (node (ref "V5") (pin "8") (pinfunction "PK_8") (pintype "passive"))
    )
    (net (code "8") (name "Net-(C2-Pad1)") (class "Default")
      (node (ref "C2") (pin "1") (pinfunction "1_1") (pintype "passive"))
      (node (ref "S2") (pin "3") (pinfunction "3_3") (pintype "passive"))
    )
    (net (code "9") (name "Net-(C4-Pad1)") (class "Default")
      (node (ref "C4") (pin "1") (pinfunction "1_1") (pintype "passive"))
      (node (ref "S2") (pin "1") (pinfunction "1_1") (pintype "passive"))
    )
    (net (code "10") (name "Net-(C5-Pad2)") (class "Default")
      (node (ref "C5") (pin "2") (pinfunction "2_2") (pintype "passive"))
      (node (ref "R4") (pin "2") (pinfunction "2_2") (pintype "passive"))
      (node (ref "R9") (pin "2") (pinfunction "2_2") (pintype "passive"))
    )
    (net (code "11") (name "Net-(C6-Pad1)") (class "Default")
      (node (ref "C6") (pin "1") (pinfunction "1_1") (pintype "passive"))
      (node (ref "C9") (pin "1") (pinfunction "1_1") (pintype "passive"))
      (node (ref "R5") (pin "1") (pinfunction "1_1") (pintype "passive"))
    )
    (net (code "12") (name "Net-(C10-Pad2)") (class "Default")
      (node (ref "C10") (pin "2") (pinfunction "2_2") (pintype "passive"))
      (node (ref "R16") (pin "1") (pinfunction "1_1") (pintype "passive"))
      (node (ref "R21") (pin "2") (pinfunction "2_2") (pintype "passive"))
    )
    (net (code "13") (name "Net-(C22-Pad2)") (class "Default")
      (node (ref "C22") (pin "2") (pinfunction "2_2") (pintype "passive"))
      (node (ref "R35") (pin "1") (pinfunction "1_1") (pintype "passive"))
      (node (ref "R36") (pin "2") (pinfunction "2_2") (pintype "passive"))
    )
    (net (code "14") (name "Net-(D1-A)") (class "Default")
      (node (ref "D1") (pin "1") (pinfunction "A_1") (pintype "passive"))
      (node (ref "D2") (pin "2") (pinfunction "K_2") (pintype "passive"))
    )
    (net (code "15") (name "Net-(D1-K)") (class "Default")
      (node (ref "D1") (pin "2") (pinfunction "K_2") (pintype "passive"))
      (node (ref "T1") (pin "1") (pinfunction "A1_1") (pintype "passive"))
      (node (ref "V1") (pin "3") (pinfunction "PA_3") (pintype "passive"))
    )
    (net (code "16") (name "Net-(D2-A)") (class "Default")
      (node (ref "D2") (pin "1") (pinfunction "A_1") (pintype "passive"))
      (node (ref "D3") (pin "2") (pinfunction "K_2") (pintype "passive"))
    )
    (net (code "17") (name "Net-(D4-K)") (class "Default")
      (node (ref "D4") (pin "2") (pinfunction "K_2") (pintype "passive"))
      (node (ref "D5") (pin "1") (pinfunction "A_1") (pintype "passive"))
    )
    (net (code "18") (name "Net-(D5-K)") (class "Default")
      (node (ref "D5") (pin "2") (pinfunction "K_2") (pintype "passive"))
      (node (ref "D6") (pin "1") (pinfunction "A_1") (pintype "passive"))
    )
    (net (code "19") (name "Net-(D6-K)") (class "Default")
      (node (ref "D6") (pin "2") (pinfunction "K_2") (pintype "passive"))
      (node (ref "T1") (pin "3") (pinfunction "A2_3") (pintype "passive"))
      (node (ref "V5") (pin "3") (pinfunction "PA_3") (pintype "passive"))
    )
    (net (code "20") (name "Net-(D7-A)") (class "Default")
      (node (ref "D7") (pin "1") (pinfunction "A_1") (pintype "passive"))
      (node (ref "T2") (pin "4") (pinfunction "Sec_355V_+_4") (pintype "passive"))
    )
    (net (code "21") (name "Net-(D7-K)") (class "Default")
      (node (ref "D7") (pin "2") (pinfunction "K_2") (pintype "passive"))
      (node (ref "D8") (pin "1") (pinfunction "A_1") (pintype "passive"))
    )
    (net (code "22") (name "Net-(D9-A)") (class "Default")
      (node (ref "D9") (pin "1") (pinfunction "A_1") (pintype "passive"))
      (node (ref "T2") (pin "7") (pinfunction "Sec_355V_-_7") (pintype "passive"))
    )
    (net (code "23") (name "Net-(D10-A)") (class "Default")
      (node (ref "D10") (pin "1") (pinfunction "A_1") (pintype "passive"))
      (node (ref "D9") (pin "2") (pinfunction "K_2") (pintype "passive"))
    )
    (net (code "24") (name "Net-(D10-K)") (class "Default")
      (node (ref "C15") (pin "1") (pinfunction "1_1") (pintype "passive"))
      (node (ref "C16") (pin "1") (pinfunction "1_1") (pintype "passive"))
      (node (ref "D10") (pin "2") (pinfunction "K_2") (pintype "passive"))
      (node (ref "D8") (pin "2") (pinfunction "K_2") (pintype "passive"))
      (node (ref "J3") (pin "1") (pinfunction "1_1") (pintype "passive"))
      (node (ref "R32") (pin "2") (pinfunction "2_2") (pintype "passive"))
      (node (ref "S3") (pin "1") (pinfunction "COMMON_1") (pintype "passive"))
    )
    (net (code "25") (name "Net-(D11-A)") (class "Default")
      (node (ref "C21") (pin "2") (pinfunction "2_2") (pintype "passive"))
      (node (ref "D11") (pin "1") (pinfunction "A_1") (pintype "passive"))
      (node (ref "R35") (pin "2") (pinfunction "2_2") (pintype "passive"))
    )
    (net (code "26") (name "Net-(D11-K)") (class "Default")
      (node (ref "D11") (pin "2") (pinfunction "K_2") (pintype "passive"))
      (node (ref "R34") (pin "1") (pinfunction "1_1") (pintype "passive"))
    )
    (net (code "27") (name "Net-(J2-T)") (class "Default")
      (node (ref "J2") (pin "1") (pinfunction "T_1") (pintype "output"))
      (node (ref "R7") (pin "2") (pinfunction "2_2") (pintype "passive"))
      (node (ref "V2") (pin "7") (pinfunction "TG_7") (pintype "passive"))
    )
    (net (code "28") (name "Net-(J6-T)") (class "Default")
      (node (ref "J6") (pin "1") (pinfunction "T_1") (pintype "passive"))
      (node (ref "J7") (pin "1") (pinfunction "T_1") (pintype "passive"))
      (node (ref "S1") (pin "2") (pinfunction "2_2") (pintype "passive"))
    )
    (net (code "29") (name "Net-(J9-L)") (class "Default")
      (node (ref "J9") (pin "1") (pinfunction "L_1") (pintype "power_in"))
      (node (ref "T2") (pin "3") (pinfunction "Pri-_3") (pintype "passive"))
    )
    (net (code "30") (name "Net-(J9-N)") (class "Default")
      (node (ref "F1") (pin "1") (pinfunction "1_1") (pintype "passive"))
      (node (ref "J9") (pin "2") (pinfunction "N_2") (pintype "power_in"))
    )
    (net (code "31") (name "Net-(R3-TOP)") (class "Default")
      (node (ref "C1") (pin "2") (pinfunction "2_2") (pintype "passive"))
      (node (ref "R3") (pin "1") (pinfunction "TOP_1") (pintype "passive"))
    )
    (net (code "32") (name "Net-(R11-Pad1)") (class "Default")
      (node (ref "R11") (pin "1") (pinfunction "1_1") (pintype "passive"))
      (node (ref "R13") (pin "1") (pinfunction "1_1") (pintype "passive"))
      (node (ref "R14") (pin "2") (pinfunction "2_2") (pintype "passive"))
      (node (ref "R20") (pin "2") (pinfunction "2_2") (pintype "passive"))
    )
    (net (code "33") (name "Net-(R12-BOT)") (class "Default")
      (node (ref "C9") (pin "2") (pinfunction "2_2") (pintype "passive"))
      (node (ref "R12") (pin "2") (pinfunction "BOT_2") (pintype "passive"))
      (node (ref "R24") (pin "3") (pinfunction "TAP_3") (pintype "passive"))
    )
    (net (code "34") (name "Net-(R12-TAP)") (class "Default")
      (node (ref "C6") (pin "2") (pinfunction "2_2") (pintype "passive"))
      (node (ref "R12") (pin "3") (pinfunction "TAP_3") (pintype "passive"))
      (node (ref "R3") (pin "2") (pinfunction "BOT_2") (pintype "passive"))
    )
    (net (code "35") (name "Net-(R19-TAP)") (class "Default")
      (node (ref "R19") (pin "3") (pinfunction "TAP_3") (pintype "passive"))
      (node (ref "S2") (pin "2") (pinfunction "2_2") (pintype "passive"))
      (node (ref "V2") (pin "2") (pinfunction "TG_2") (pintype "passive"))
    )
    (net (code "36") (name "Net-(R19-TOP)") (class "Default")
      (node (ref "C2") (pin "2") (pinfunction "2_2") (pintype "passive"))
      (node (ref "C4") (pin "2") (pinfunction "2_2") (pintype "passive"))
      (node (ref "R19") (pin "1") (pinfunction "TOP_1") (pintype "passive"))
      (node (ref "R3") (pin "3") (pinfunction "TAP_3") (pintype "passive"))
    )
    (net (code "37") (name "Net-(R26-BOT)") (class "Default")
      (node (ref "C11") (pin "1") (pinfunction "1_1") (pintype "passive"))
      (node (ref "R13") (pin "2") (pinfunction "2_2") (pintype "passive"))
      (node (ref "R26") (pin "2") (pinfunction "BOT_2") (pintype "passive"))
      (node (ref "S1") (pin "1") (pinfunction "1_1") (pintype "passive"))
      (node (ref "T1") (pin "5") (pinfunction "8_ohms_5") (pintype "passive"))
    )
    (net (code "38") (name "Net-(R26-TAP)") (class "Default")
      (node (ref "C14") (pin "2") (pinfunction "2_2") (pintype "passive"))
      (node (ref "R26") (pin "3") (pinfunction "TAP_3") (pintype "passive"))
    )
    (net (code "39") (name "Net-(R28-Pad2)") (class "Default")
      (node (ref "R28") (pin "2") (pinfunction "2_2") (pintype "passive"))
      (node (ref "R29") (pin "1") (pinfunction "1_1") (pintype "passive"))
    )
    (net (code "40") (name "Net-(R32-Pad1)") (class "Default")
      (node (ref "R32") (pin "1") (pinfunction "1_1") (pintype "passive"))
      (node (ref "R33") (pin "2") (pinfunction "2_2") (pintype "passive"))
    )
    (net (code "41") (name "Net-(R37-BOT)") (class "Default")
      (node (ref "R36") (pin "1") (pinfunction "1_1") (pintype "passive"))
      (node (ref "R37") (pin "2") (pinfunction "BOT_2") (pintype "passive"))
    )
    (net (code "42") (name "Net-(T1-4_ohms)") (class "Default")
      (node (ref "S1") (pin "3") (pinfunction "3_3") (pintype "passive"))
      (node (ref "T1") (pin "6") (pinfunction "4_ohms_6") (pintype "passive"))
    )
    (net (code "43") (name "Net-(T1-16_omhs)") (class "Default")
      (node (ref "S1") (pin "4") (pinfunction "4_4") (pintype "passive"))
      (node (ref "T1") (pin "4") (pinfunction "16_omhs_4") (pintype "passive"))
    )
    (net (code "44") (name "Net-(T2-3.15V+)") (class "Default")
      (node (ref "T2") (pin "8") (pinfunction "3.15V+_8") (pintype "passive"))
      (node (ref "V1") (pin "2") (pinfunction "H1_2") (pintype "passive"))
      (node (ref "V2") (pin "9") (pinfunction "H2_9") (pintype "passive"))
      (node (ref "V3") (pin "9") (pinfunction "H2_9") (pintype "passive"))
      (node (ref "V4") (pin "9") (pinfunction "H2_9") (pintype "passive"))
      (node (ref "V5") (pin "7") (pinfunction "H2_7") (pintype "passive"))
    )
    (net (code "45") (name "Net-(T2-3.15V_-)") (class "Default")
      (node (ref "T2") (pin "10") (pinfunction "3.15V_-_10") (pintype "passive"))
      (node (ref "V1") (pin "7") (pinfunction "H2_7") (pintype "passive"))
      (node (ref "V2") (pin "4") (pinfunction "H1_4") (pintype "passive"))
      (node (ref "V2") (pin "5") (pinfunction "H3_5") (pintype "passive"))
      (node (ref "V3") (pin "4") (pinfunction "H1_4") (pintype "passive"))
      (node (ref "V3") (pin "5") (pinfunction "H3_5") (pintype "passive"))
      (node (ref "V4") (pin "4") (pinfunction "H1_4") (pintype "passive"))
      (node (ref "V4") (pin "5") (pinfunction "H3_5") (pintype "passive"))
      (node (ref "V5") (pin "2") (pinfunction "H1_2") (pintype "passive"))
    )
    (net (code "46") (name "Net-(T2-Pri+220V)") (class "Default")
      (node (ref "F1") (pin "2") (pinfunction "2_2") (pintype "passive"))
      (node (ref "T2") (pin "1") (pinfunction "Pri+220V_1") (pintype "passive"))
    )
    (net (code "47") (name "Net-(T2-Sec_55V_+)") (class "Default")
      (node (ref "R34") (pin "2") (pinfunction "2_2") (pintype "passive"))
      (node (ref "T2") (pin "6") (pinfunction "Sec_55V_+_6") (pintype "passive"))
    )
    (net (code "48") (name "Net-(V1A-PG)") (class "Default")
      (node (ref "R4") (pin "1") (pinfunction "1_1") (pintype "passive"))
      (node (ref "V1") (pin "5") (pinfunction "PG_5") (pintype "passive"))
    )
    (net (code "49") (name "Net-(V1A-PSG)") (class "Default")
      (node (ref "R10") (pin "2") (pinfunction "2_2") (pintype "passive"))
      (node (ref "V1") (pin "4") (pinfunction "PSG_4") (pintype "passive"))
    )
    (net (code "50") (name "Net-(V2A-TA)") (class "Default")
      (node (ref "C7") (pin "1") (pinfunction "1_1") (pintype "passive"))
      (node (ref "R6") (pin "1") (pinfunction "1_1") (pintype "passive"))
      (node (ref "V2") (pin "1") (pinfunction "TA_1") (pintype "passive"))
    )
    (net (code "51") (name "Net-(V2A-TK)") (class "Default")
      (node (ref "C13") (pin "1") (pinfunction "1_1") (pintype "passive"))
      (node (ref "R25") (pin "2") (pinfunction "2_2") (pintype "passive"))
      (node (ref "V2") (pin "3") (pinfunction "TK_3") (pintype "passive"))
    )
    (net (code "52") (name "Net-(V2B-TA)") (class "Default")
      (node (ref "C1") (pin "1") (pinfunction "1_1") (pintype "passive"))
      (node (ref "R1") (pin "1") (pinfunction "1_1") (pintype "passive"))
      (node (ref "R5") (pin "2") (pinfunction "2_2") (pintype "passive"))
      (node (ref "V2") (pin "6") (pinfunction "TA_6") (pintype "passive"))
    )
    (net (code "53") (name "Net-(V2B-TK)") (class "Default")
      (node (ref "C12") (pin "1") (pinfunction "1_1") (pintype "passive"))
      (node (ref "R22") (pin "2") (pinfunction "2_2") (pintype "passive"))
      (node (ref "V2") (pin "8") (pinfunction "TK_8") (pintype "passive"))
    )
    (net (code "54") (name "Net-(V3A-TA)") (class "Default")
      (node (ref "C3") (pin "1") (pinfunction "1_1") (pintype "passive"))
      (node (ref "R2") (pin "1") (pinfunction "1_1") (pintype "passive"))
      (node (ref "V3") (pin "1") (pinfunction "TA_1") (pintype "passive"))
    )
    (net (code "55") (name "Net-(V3A-TG)") (class "Default")
      (node (ref "C7") (pin "2") (pinfunction "2_2") (pintype "passive"))
      (node (ref "R18") (pin "2") (pinfunction "2_2") (pintype "passive"))
      (node (ref "V3") (pin "2") (pinfunction "TG_2") (pintype "passive"))
    )
    (net (code "56") (name "Net-(V3A-TK)") (class "Default")
      (node (ref "R23") (pin "2") (pinfunction "2_2") (pintype "passive"))
      (node (ref "V3") (pin "3") (pinfunction "TK_3") (pintype "passive"))
    )
    (net (code "57") (name "Net-(V4A-TA)") (class "Default")
      (node (ref "C10") (pin "1") (pinfunction "1_1") (pintype "passive"))
      (node (ref "C8") (pin "1") (pinfunction "1_1") (pintype "passive"))
      (node (ref "R15") (pin "1") (pinfunction "1_1") (pintype "passive"))
      (node (ref "V4") (pin "1") (pinfunction "TA_1") (pintype "passive"))
    )
    (net (code "58") (name "Net-(V4A-TG)") (class "Default")
      (node (ref "C11") (pin "2") (pinfunction "2_2") (pintype "passive"))
      (node (ref "R20") (pin "1") (pinfunction "1_1") (pintype "passive"))
      (node (ref "V4") (pin "2") (pinfunction "TG_2") (pintype "passive"))
    )
    (net (code "59") (name "Net-(V4A-TK)") (class "Default")
      (node (ref "R14") (pin "1") (pinfunction "1_1") (pintype "passive"))
      (node (ref "V4") (pin "3") (pinfunction "TK_3") (pintype "passive"))
      (node (ref "V4") (pin "8") (pinfunction "TK_8") (pintype "passive"))
    )
    (net (code "60") (name "Net-(V4B-TA)") (class "Default")
      (node (ref "C5") (pin "1") (pinfunction "1_1") (pintype "passive"))
      (node (ref "C8") (pin "2") (pinfunction "2_2") (pintype "passive"))
      (node (ref "R8") (pin "2") (pinfunction "2_2") (pintype "passive"))
      (node (ref "V4") (pin "6") (pinfunction "TA_6") (pintype "passive"))
    )
    (net (code "61") (name "Net-(V4B-TG)") (class "Default")
      (node (ref "C3") (pin "2") (pinfunction "2_2") (pintype "passive"))
      (node (ref "R11") (pin "2") (pinfunction "2_2") (pintype "passive"))
      (node (ref "V4") (pin "7") (pinfunction "TG_7") (pintype "passive"))
    )
    (net (code "62") (name "Net-(V5A-PG)") (class "Default")
      (node (ref "R21") (pin "1") (pinfunction "1_1") (pintype "passive"))
      (node (ref "V5") (pin "5") (pinfunction "PG_5") (pintype "passive"))
    )
    (net (code "63") (name "Net-(V5A-PSG)") (class "Default")
      (node (ref "R17") (pin "1") (pinfunction "1_1") (pintype "passive"))
      (node (ref "V5") (pin "4") (pinfunction "PSG_4") (pintype "passive"))
    )
    (net (code "64") (name "unconnected-(R12-TOP-Pad1)") (class "Default")
      (node (ref "R12") (pin "1") (pinfunction "TOP_1") (pintype "passive"))
    )
    (net (code "65") (name "unconnected-(R24-TOP-Pad1)") (class "Default")
      (node (ref "R24") (pin "1") (pinfunction "TOP_1") (pintype "passive"))
    )
  )
)
